# Steering_Wheel_Interface_Analog_Inputs.net
KiCad netlist of a schematic drawn in Altium Designer
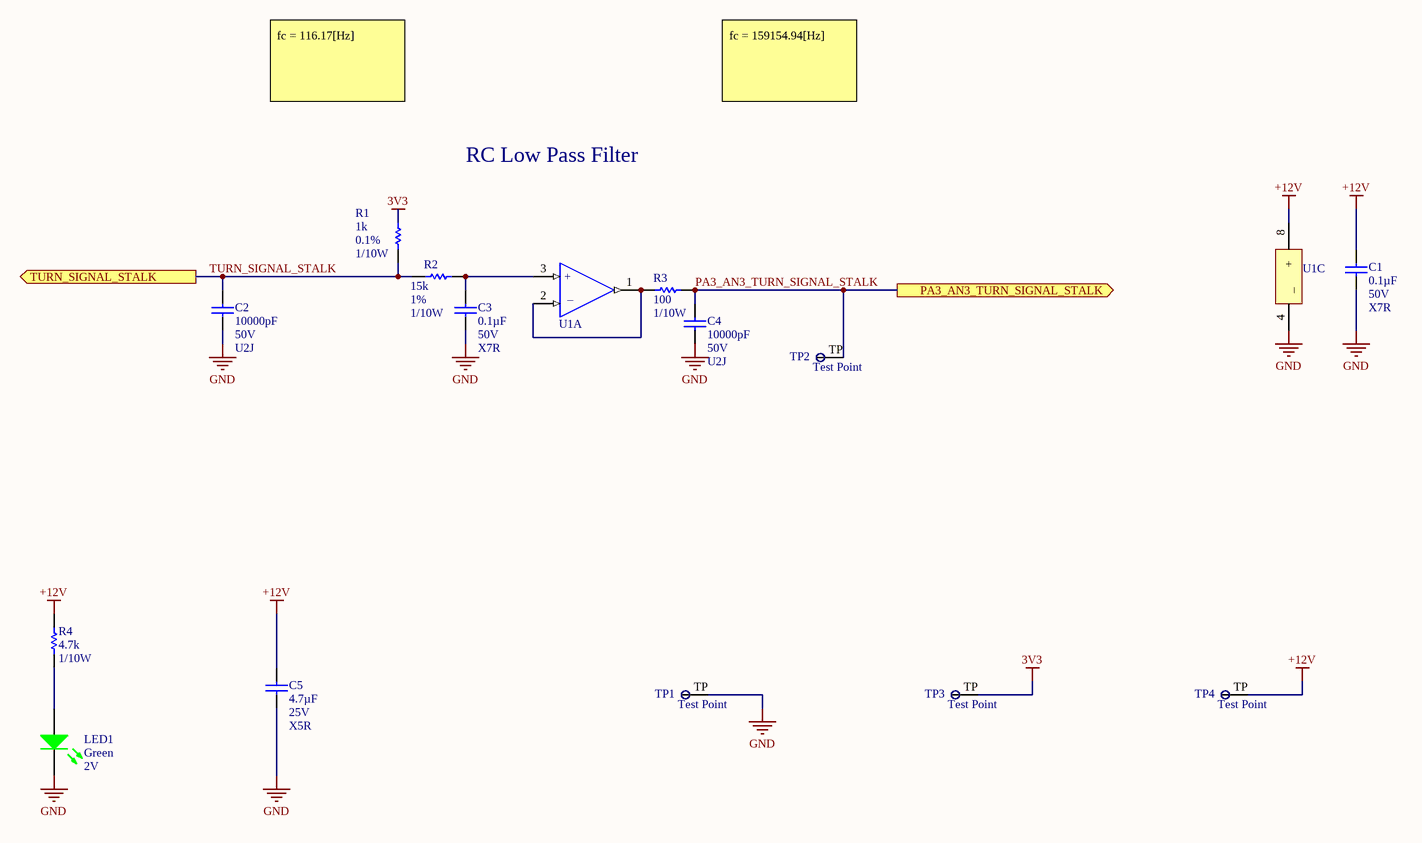
[diagram p0: Steering Wheel Interface Analog Inputs.SchDoc]

(export (version "E")
  (design (tool "Eeschema 10.0.6"))
  (components
    (comp (ref "C1")
      (value "CAP CER 0.1UF 50V 10% X7R 0603")
      (footprint "CAP, 0603")
      (description "0.10µF ±10% 50V Ceramic Capacitor X7R 0603 (1608 Metric)")
      (fields
        (field (name "TOLERANCE") "±10%")
        (field (name "CAPACITANCE") "0.1µF")
        (field (name "VOLTAGE") "50V")
        (field (name "TEMPERATURE COEFFICIENT") "X7R")
      )
      (libsource (lib "Schematic Diagrams") (part "CAP CER 0.1UF 50V 10% X7R 0603"))
    )
    (comp (ref "C2")
      (value "CAP CER 10nF 50V 5% X7R 0603")
      (footprint "CAP, 0603")
      (description "10000pF ±5% 50V Ceramic Capacitor U2J 0603 (1608 Metric)")
      (fields
        (field (name "TOLERANCE") "±5%")
        (field (name "CAPACITANCE") "10000pF")
        (field (name "VOLTAGE") "50V")
        (field (name "TEMPERATURE COEFFICIENT") "U2J")
      )
      (libsource (lib "Schematic Diagrams") (part "CAP CER 10nF 50V 5% X7R 0603"))
    )
    (comp (ref "C3")
      (value "CAP CER 0.1UF 50V 10% X7R 0603")
      (footprint "CAP, 0603")
      (description "0.10µF ±10% 50V Ceramic Capacitor X7R 0603 (1608 Metric)")
      (fields
        (field (name "TOLERANCE") "±10%")
        (field (name "CAPACITANCE") "0.1µF")
        (field (name "VOLTAGE") "50V")
        (field (name "TEMPERATURE COEFFICIENT") "X7R")
      )
      (libsource (lib "Schematic Diagrams") (part "CAP CER 0.1UF 50V 10% X7R 0603"))
    )
    (comp (ref "C4")
      (value "CAP CER 10nF 50V 5% X7R 0603")
      (footprint "CAP, 0603")
      (description "10000pF ±5% 50V Ceramic Capacitor U2J 0603 (1608 Metric)")
      (fields
        (field (name "TOLERANCE") "±5%")
        (field (name "CAPACITANCE") "10000pF")
        (field (name "VOLTAGE") "50V")
        (field (name "TEMPERATURE COEFFICIENT") "U2J")
      )
      (libsource (lib "Schematic Diagrams") (part "CAP CER 10nF 50V 5% X7R 0603"))
    )
    (comp (ref "C5")
      (value "CAP CER 4.7UF 25V 10% X5R 0603")
      (footprint "CAP, 0603")
      (description "4.7µF ±10% 25V Ceramic Capacitor X5R 0603 (1608 Metric)")
      (fields
        (field (name "TOLERANCE") "±10%")
        (field (name "CAPACITANCE") "4.7µF")
        (field (name "VOLTAGE") "25V")
        (field (name "TEMPERATURE COEFFICIENT") "X5R")
      )
      (libsource (lib "Schematic Diagrams") (part "CAP CER 4.7UF 25V 10% X5R 0603"))
    )
    (comp (ref "LED1")
      (value "LED GREEN CLEAR 2V 0603")
      (footprint "LED_0603")
      (description "Green 572nm LED Indication - Discrete 2V 0603 (1608 Metric)")
      (fields
        (field (name "MANUFACTURER") "Wurth Electronics Inc.")
        (field (name "MANUFACTURER PART NUMBER") "150060VS75000")
        (field (name "COLOR") "Green")
        (field (name "VOLTAGE - FORWARD (VF) (TYP)") "2V")
      )
      (libsource (lib "Schematic Diagrams") (part "LED GREEN CLEAR 2V 0603"))
    )
    (comp (ref "R1")
      (value "RES SMD 1K OHM 0.1% 1/10W 0603")
      (footprint "RES, 0603")
      (description "1 kOhms ±0.1% 0.1W, 1/10W Chip Resistor 0603 (1608 Metric) Automotive AEC-Q200 Thin Film")
      (fields
        (field (name "MANUFACTURER") "Panasonic")
        (field (name "MANUFACTURER PART NUMBER") "ERA3AEB102V")
        (field (name "RESISTANCE") "1k")
        (field (name "TOLERANCE") "0.1%")
        (field (name "POWER RATING") "1/10W")
      )
      (libsource (lib "Schematic Diagrams") (part "RES SMD 1K OHM 0.1% 1/10W 0603"))
    )
    (comp (ref "R2")
      (value "RES SMD 15K OHM 1% 1/10W 0603")
      (footprint "RES, 0603")
      (description "15 kOhms ±1% 0.1W, 1/10W Chip Resistor 0603 (1608 Metric) Moisture Resistant Thick Film")
      (fields
        (field (name "RESISTANCE") "15k")
        (field (name "TOLERANCE") "1%")
        (field (name "MAX POWER DISSIPATION") "1/10W")
        (field (name "MANUFACTURER") "Yageo")
        (field (name "MANUFACTURER PART NUMBER") "RC0603FR-0715KL")
      )
      (libsource (lib "Schematic Diagrams") (part "RES SMD 15K OHM 1% 1/10W 0603"))
    )
    (comp (ref "R3")
      (value "RES 100 OHM 1% 1/10W 0603")
      (footprint "RES, 0603")
      (description "100 Ohm ±1% 0.1W, 1/10W Chip Resistor 0603 (1608 Metric) Moisture Resistant Thick Film")
      (fields
        (field (name "TOLERANCE") "±1%")
        (field (name "RESISTANCE") "100")
        (field (name "POWER") "1/10W")
      )
      (libsource (lib "Schematic Diagrams") (part "RES 100 OHM 1% 1/10W 0603"))
    )
    (comp (ref "R4")
      (value "RES 4.7K OHM 1% 1/10W 0603")
      (footprint "RES, 0603")
      (description "4.7k Ohm ±1% 0.1W, 1/10W Chip Resistor 0603 (1608 Metric) Moisture Resistant Thick Film")
      (fields
        (field (name "TOLERANCE") "±1%")
        (field (name "RESISTANCE (OHMS)") "4.7k")
        (field (name "POWER (WATTS)") "1/10W")
      )
      (libsource (lib "Schematic Diagrams") (part "RES 4.7K OHM 1% 1/10W 0603"))
    )
    (comp (ref "TP1")
      (value "Test Point")
      (footprint "Test Point")
      (libsource (lib "Schematic Diagrams") (part "Test Point"))
    )
    (comp (ref "TP2")
      (value "Test Point")
      (footprint "Test Point")
      (libsource (lib "Schematic Diagrams") (part "Test Point"))
    )
    (comp (ref "TP3")
      (value "Test Point")
      (footprint "Test Point")
      (libsource (lib "Schematic Diagrams") (part "Test Point"))
    )
    (comp (ref "TP4")
      (value "Test Point")
      (footprint "Test Point")
      (libsource (lib "Schematic Diagrams") (part "Test Point"))
    )
    (comp (ref "U1")
      (value "IC OP AMP DUAL GP RR 10MHZ 8-VSSOP")
      (footprint "IC OP AMP DUAL 8-VSSOP")
      (description "General Purpose Amplifier 2 Circuit Rail-to-Rail 8-VSSOP")
      (fields
        (field (name "MANUFACTURER") "Texas Instruments")
        (field (name "MANUFACTURER PART NUMBER") "OPA2197IDGKR")
      )
      (libsource (lib "Schematic Diagrams") (part "IC OP AMP DUAL GP RR 10MHZ 8-VSSOP"))
    )
  )
  (nets
    (net (code "1") (name "+12V") (class "Default")
      (node (ref "C1") (pin "1") (pinfunction "1_1") (pintype "passive"))
      (node (ref "C5") (pin "1") (pinfunction "1_1") (pintype "passive"))
      (node (ref "R4") (pin "1") (pinfunction "1_1") (pintype "passive"))
      (node (ref "TP4") (pin "TP") (pinfunction "1_TP") (pintype "passive"))
      (node (ref "U1") (pin "8") (pinfunction "+_8") (pintype "power_in"))
    )
    (net (code "2") (name "/PA3_AN3_TURN_SIGNAL_STALK") (class "Default")
      (node (ref "C4") (pin "1") (pinfunction "1_1") (pintype "passive"))
      (node (ref "R3") (pin "1") (pinfunction "1_1") (pintype "passive"))
      (node (ref "TP2") (pin "TP") (pinfunction "1_TP") (pintype "passive"))
    )
    (net (code "3") (name "/TURN_SIGNAL_STALK") (class "Default")
      (node (ref "C2") (pin "1") (pinfunction "1_1") (pintype "passive"))
      (node (ref "R1") (pin "2") (pinfunction "2_2") (pintype "passive"))
      (node (ref "R2") (pin "2") (pinfunction "2_2") (pintype "passive"))
    )
    (net (code "4") (name "3V3") (class "Default")
      (node (ref "R1") (pin "1") (pinfunction "1_1") (pintype "passive"))
      (node (ref "TP3") (pin "TP") (pinfunction "1_TP") (pintype "passive"))
    )
    (net (code "5") (name "GND") (class "Default")
      (node (ref "C1") (pin "2") (pinfunction "2_2") (pintype "passive"))
      (node (ref "C2") (pin "2") (pinfunction "2_2") (pintype "passive"))
      (node (ref "C3") (pin "2") (pinfunction "2_2") (pintype "passive"))
      (node (ref "C4") (pin "2") (pinfunction "2_2") (pintype "passive"))
      (node (ref "C5") (pin "2") (pinfunction "2_2") (pintype "passive"))
      (node (ref "LED1") (pin "2") (pinfunction "K_2") (pintype "passive"))
      (node (ref "TP1") (pin "TP") (pinfunction "1_TP") (pintype "passive"))
      (node (ref "U1") (pin "4") (pinfunction "__4") (pintype "power_in"))
    )
    (net (code "6") (name "Net-(LED1-A)") (class "Default")
      (node (ref "LED1") (pin "1") (pinfunction "A_1") (pintype "passive"))
      (node (ref "R4") (pin "2") (pinfunction "2_2") (pintype "passive"))
    )
    (net (code "7") (name "Net-(U1A-+IN_A)") (class "Default")
      (node (ref "C3") (pin "1") (pinfunction "1_1") (pintype "passive"))
      (node (ref "R2") (pin "1") (pinfunction "1_1") (pintype "passive"))
      (node (ref "U1") (pin "3") (pinfunction "+IN_A_3") (pintype "input"))
    )
    (net (code "8") (name "Net-(U1A--IN_A)") (class "Default")
      (node (ref "R3") (pin "2") (pinfunction "2_2") (pintype "passive"))
      (node (ref "U1") (pin "1") (pinfunction "OUT_A_1") (pintype "output"))
      (node (ref "U1") (pin "2") (pinfunction "-IN_A_2") (pintype "input"))
    )
  )
)
